# MagicMirror.net
KiCad netlist of a schematic drawn in Altium Designer
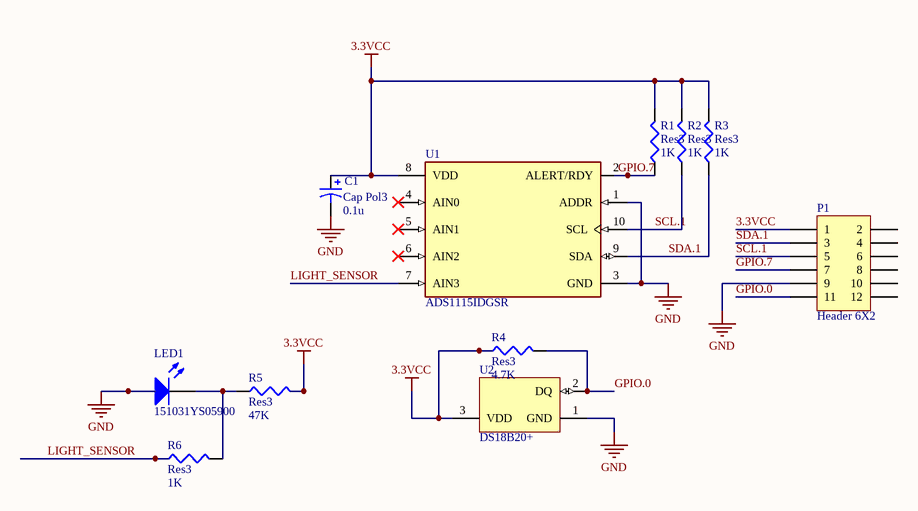
[diagram p0: MagicMirror.SchDoc]

(export (version "E")
  (design (tool "Eeschema 10.0.6"))
  (components
    (comp (ref "C1")
      (value "Cap Pol3")
      (footprint "C0805")
      (description "Polarized Capacitor (Surface Mount)")
      (fields (field (name "ALTIUM_VALUE") "0.1u") (field (name "PUBLISHER") "Altium Limited"))
      (libsource (lib "Miscellaneous Devices") (part "Cap Pol3"))
    )
    (comp (ref "LED1")
      (value "151031YS05900")
      (footprint "Type 3mm")
      (description "THT LED round mono-color color lens, WL-TMRC, Yellow")
      (fields (field (name "MANUFACTURER") "Wuerth Elektronik"))
      (libsource (lib "Altium Content Vault") (part "WE-LED_K1A2-2"))
    )
    (comp (ref "P1")
      (value "Header 6X2")
      (footprint "HDR2X6")
      (description "Header, 6-Pin, Dual row")
      (fields (field (name "PUBLISHER") "Altium Limited"))
      (libsource (lib "Miscellaneous Connectors") (part "Header 6X2"))
    )
    (comp (ref "R1")
      (value "Res3")
      (footprint "J1-0603")
      (description "Resistor")
      (fields (field (name "ALTIUM_VALUE") "1K") (field (name "PUBLISHER") "Altium Limited"))
      (libsource (lib "Miscellaneous Devices") (part "Res3"))
    )
    (comp (ref "R2")
      (value "Res3")
      (footprint "J1-0603")
      (description "Resistor")
      (fields (field (name "ALTIUM_VALUE") "1K") (field (name "PUBLISHER") "Altium Limited"))
      (libsource (lib "Miscellaneous Devices") (part "Res3"))
    )
    (comp (ref "R3")
      (value "Res3")
      (footprint "J1-0603")
      (description "Resistor")
      (fields (field (name "ALTIUM_VALUE") "1K") (field (name "PUBLISHER") "Altium Limited"))
      (libsource (lib "Miscellaneous Devices") (part "Res3"))
    )
    (comp (ref "R4")
      (value "Res3")
      (footprint "J1-0603")
      (description "Resistor")
      (fields (field (name "ALTIUM_VALUE") "4.7K") (field (name "PUBLISHER") "Altium Limited"))
      (libsource (lib "Miscellaneous Devices") (part "Res3"))
    )
    (comp (ref "R5")
      (value "Res3")
      (footprint "J1-0603")
      (description "Resistor")
      (fields (field (name "ALTIUM_VALUE") "47K") (field (name "PUBLISHER") "Altium Limited"))
      (libsource (lib "Miscellaneous Devices") (part "Res3"))
    )
    (comp (ref "R6")
      (value "Res3")
      (footprint "J1-0603")
      (description "Resistor")
      (fields (field (name "ALTIUM_VALUE") "1K") (field (name "PUBLISHER") "Altium Limited"))
      (libsource (lib "Miscellaneous Devices") (part "Res3"))
    )
    (comp (ref "U1")
      (value "ADS1115IDGSR")
      (footprint "FP-DGS0010A-IPC_B")
      (description "IC ADC 16BIT SIGMA-DELTA 10VSSOP")
      (libsource (lib "Altium Content Vault") (part "1442cd67780685bba1a77ae27c88037"))
    )
    (comp (ref "U2")
      (value "DS18B20+")
      (footprint "Q3+1")
      (libsource (lib "Altium Content Vault") (part "SEN-TEMP-DS1821-SIL3"))
    )
  )
  (nets
    (net (code "1") (name "/GPIO.0") (class "Default")
      (node (ref "P1") (pin "11") (pinfunction "11_11") (pintype "passive"))
      (node (ref "R4") (pin "2") (pinfunction "2_2") (pintype "passive"))
      (node (ref "U2") (pin "2") (pinfunction "DQ_2") (pintype "bidirectional"))
    )
    (net (code "2") (name "/GPIO.7") (class "Default")
      (node (ref "P1") (pin "7") (pinfunction "7_7") (pintype "passive"))
      (node (ref "R1") (pin "1") (pinfunction "1_1") (pintype "passive"))
      (node (ref "U1") (pin "2") (pinfunction "ALERT/RDY_2") (pintype "open_collector"))
    )
    (net (code "3") (name "/LIGHT_SENSOR") (class "Default")
      (node (ref "R6") (pin "1") (pinfunction "1_1") (pintype "passive"))
      (node (ref "U1") (pin "7") (pinfunction "AIN3_7") (pintype "input"))
    )
    (net (code "4") (name "/SCL.1") (class "Default")
      (node (ref "P1") (pin "5") (pinfunction "5_5") (pintype "passive"))
      (node (ref "R2") (pin "1") (pinfunction "1_1") (pintype "passive"))
      (node (ref "U1") (pin "10") (pinfunction "SCL_10") (pintype "input"))
    )
    (net (code "5") (name "/SDA.1") (class "Default")
      (node (ref "P1") (pin "3") (pinfunction "3_3") (pintype "passive"))
      (node (ref "R3") (pin "1") (pinfunction "1_1") (pintype "passive"))
      (node (ref "U1") (pin "9") (pinfunction "SDA_9") (pintype "bidirectional"))
    )
    (net (code "6") (name "3.3VCC") (class "Default")
      (node (ref "C1") (pin "1") (pinfunction "1_1") (pintype "passive"))
      (node (ref "P1") (pin "1") (pinfunction "1_1") (pintype "passive"))
      (node (ref "R1") (pin "2") (pinfunction "2_2") (pintype "passive"))
      (node (ref "R2") (pin "2") (pinfunction "2_2") (pintype "passive"))
      (node (ref "R3") (pin "2") (pinfunction "2_2") (pintype "passive"))
      (node (ref "R4") (pin "1") (pinfunction "1_1") (pintype "passive"))
      (node (ref "R5") (pin "2") (pinfunction "2_2") (pintype "passive"))
      (node (ref "U1") (pin "8") (pinfunction "VDD_8") (pintype "power_in"))
      (node (ref "U2") (pin "3") (pinfunction "VDD_3") (pintype "power_in"))
    )
    (net (code "7") (name "GND") (class "Default")
      (node (ref "C1") (pin "2") (pinfunction "2_2") (pintype "passive"))
      (node (ref "LED1") (pin "2") (pinfunction "A_2") (pintype "passive"))
      (node (ref "P1") (pin "9") (pinfunction "9_9") (pintype "passive"))
      (node (ref "U1") (pin "1") (pinfunction "ADDR_1") (pintype "input"))
      (node (ref "U1") (pin "3") (pinfunction "GND_3") (pintype "power_in"))
      (node (ref "U2") (pin "1") (pinfunction "GND_1") (pintype "power_in"))
    )
    (net (code "8") (name "Net-(LED1-K)") (class "Default")
      (node (ref "LED1") (pin "1") (pinfunction "K_1") (pintype "passive"))
      (node (ref "R5") (pin "1") (pinfunction "1_1") (pintype "passive"))
      (node (ref "R6") (pin "2") (pinfunction "2_2") (pintype "passive"))
    )
    (net (code "9") (name "unconnected-(P1-Pad2)") (class "Default")
      (node (ref "P1") (pin "2") (pinfunction "2_2") (pintype "passive"))
    )
    (net (code "10") (name "unconnected-(P1-Pad4)") (class "Default")
      (node (ref "P1") (pin "4") (pinfunction "4_4") (pintype "passive"))
    )
    (net (code "11") (name "unconnected-(P1-Pad6)") (class "Default")
      (node (ref "P1") (pin "6") (pinfunction "6_6") (pintype "passive"))
    )
    (net (code "12") (name "unconnected-(P1-Pad8)") (class "Default")
      (node (ref "P1") (pin "8") (pinfunction "8_8") (pintype "passive"))
    )
    (net (code "13") (name "unconnected-(P1-Pad10)") (class "Default")
      (node (ref "P1") (pin "10") (pinfunction "10_10") (pintype "passive"))
    )
    (net (code "14") (name "unconnected-(P1-Pad12)") (class "Default")
      (node (ref "P1") (pin "12") (pinfunction "12_12") (pintype "passive"))
    )
    (net (code "15") (name "unconnected-(U1-AIN0-Pad4)") (class "Default")
      (node (ref "U1") (pin "4") (pinfunction "AIN0_4") (pintype "input+no_connect"))
    )
    (net (code "16") (name "unconnected-(U1-AIN1-Pad5)") (class "Default")
      (node (ref "U1") (pin "5") (pinfunction "AIN1_5") (pintype "input+no_connect"))
    )
    (net (code "17") (name "unconnected-(U1-AIN2-Pad6)") (class "Default")
      (node (ref "U1") (pin "6") (pinfunction "AIN2_6") (pintype "input+no_connect"))
    )
  )
)
